# InputsExtras.net
KiCad netlist of a schematic drawn in Altium Designer
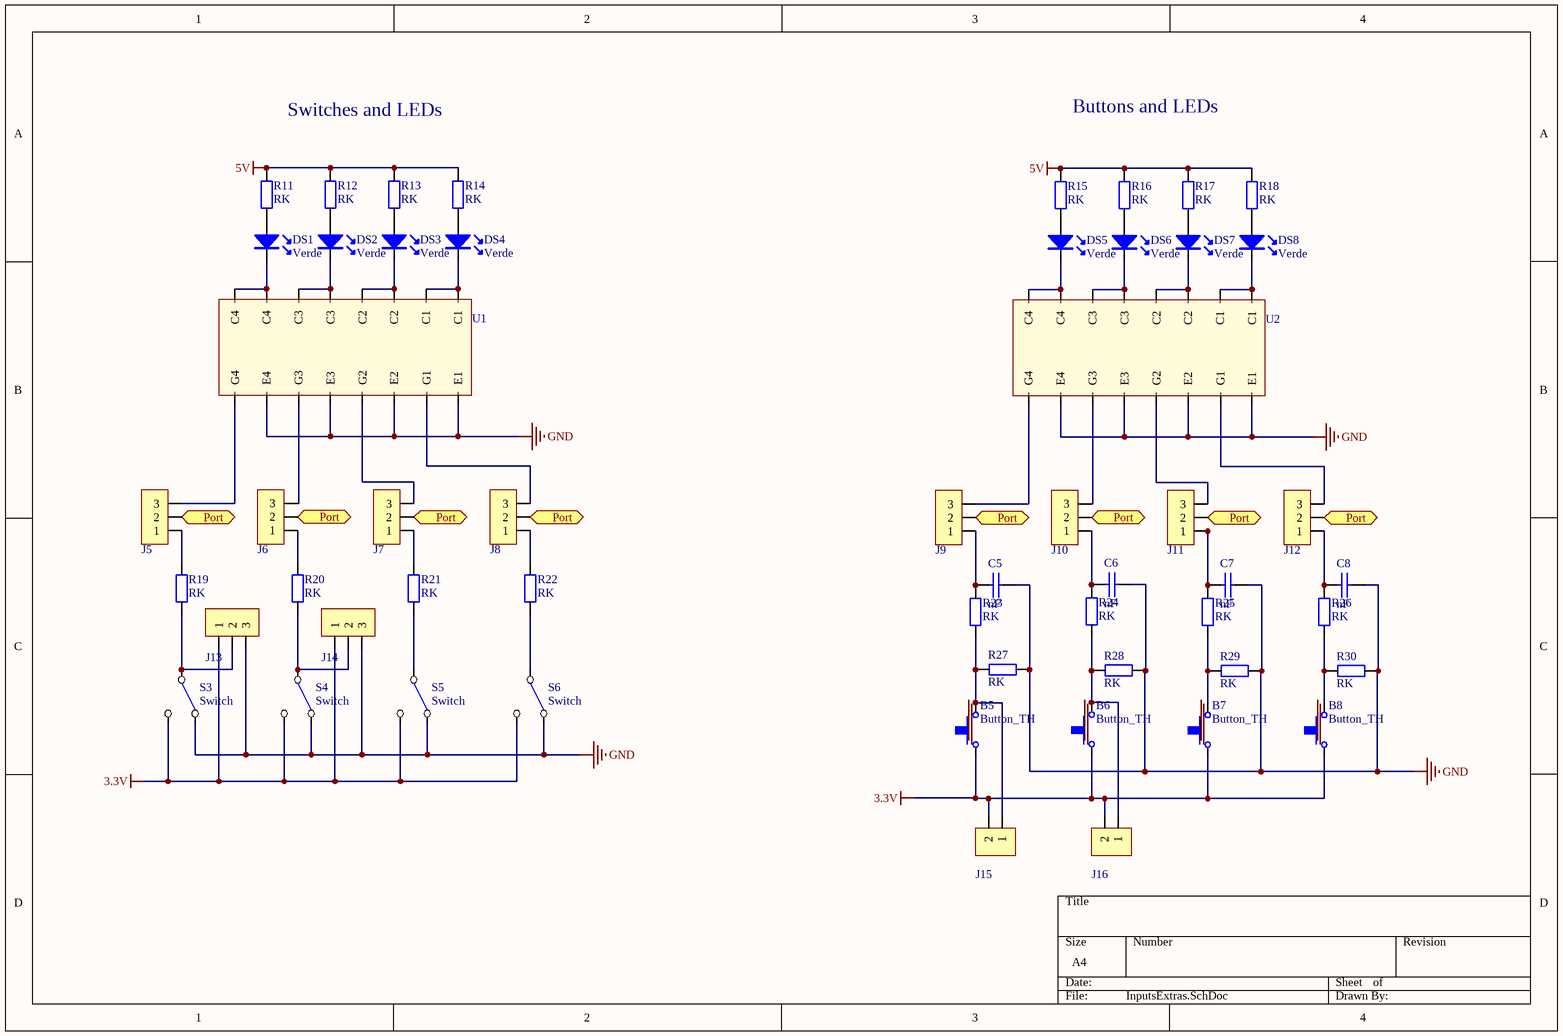
[diagram p0: InputsExtras.SchDoc]

(export (version "E")
  (design (tool "Eeschema 10.0.6"))
  (components
    (comp (ref "B5")
      (value "Button_TH")
      (footprint "ButtonTH")
      (libsource (lib "SCH_Lib") (part "Button_TH"))
    )
    (comp (ref "B6")
      (value "Button_TH")
      (footprint "ButtonTH")
      (libsource (lib "SCH_Lib") (part "Button_TH"))
    )
    (comp (ref "B7")
      (value "Button_TH")
      (footprint "ButtonTH")
      (libsource (lib "SCH_Lib") (part "Button_TH"))
    )
    (comp (ref "B8")
      (value "Button_TH")
      (footprint "ButtonTH")
      (libsource (lib "SCH_Lib") (part "Button_TH"))
    )
    (comp (ref "C5")
      (value "nF")
      (footprint "1206")
      (description "Condensador")
      (libsource (lib "SCH_Lib") (part "Condensador"))
    )
    (comp (ref "C6")
      (value "nF")
      (footprint "1206")
      (description "Condensador")
      (libsource (lib "SCH_Lib") (part "Condensador"))
    )
    (comp (ref "C7")
      (value "nF")
      (footprint "1206")
      (description "Condensador")
      (libsource (lib "SCH_Lib") (part "Condensador"))
    )
    (comp (ref "C8")
      (value "nF")
      (footprint "1206")
      (description "Condensador")
      (libsource (lib "SCH_Lib") (part "Condensador"))
    )
    (comp (ref "DS1") (value "Verde") (footprint "Led 3mm") (libsource (lib "SCH_Lib") (part "Led")))
    (comp (ref "DS2") (value "Verde") (footprint "Led 3mm") (libsource (lib "SCH_Lib") (part "Led")))
    (comp (ref "DS3") (value "Verde") (footprint "Led 3mm") (libsource (lib "SCH_Lib") (part "Led")))
    (comp (ref "DS4") (value "Verde") (footprint "Led 3mm") (libsource (lib "SCH_Lib") (part "Led")))
    (comp (ref "DS5") (value "Verde") (footprint "Led 3mm") (libsource (lib "SCH_Lib") (part "Led")))
    (comp (ref "DS6") (value "Verde") (footprint "Led 3mm") (libsource (lib "SCH_Lib") (part "Led")))
    (comp (ref "DS7") (value "Verde") (footprint "Led 3mm") (libsource (lib "SCH_Lib") (part "Led")))
    (comp (ref "DS8") (value "Verde") (footprint "Led 3mm") (libsource (lib "SCH_Lib") (part "Led")))
    (comp (ref "J5")
      (value "Cleva 2 vias")
      (footprint "con_3_100milis")
      (libsource (lib "SCH_Lib") (part "Con_3"))
    )
    (comp (ref "J6")
      (value "Cleva 2 vias")
      (footprint "con_3_100milis")
      (libsource (lib "SCH_Lib") (part "Con_3"))
    )
    (comp (ref "J7")
      (value "Cleva 2 vias")
      (footprint "con_3_100milis")
      (libsource (lib "SCH_Lib") (part "Con_3"))
    )
    (comp (ref "J8")
      (value "Cleva 2 vias")
      (footprint "con_3_100milis")
      (libsource (lib "SCH_Lib") (part "Con_3"))
    )
    (comp (ref "J9")
      (value "Cleva 2 vias")
      (footprint "con_3_100milis")
      (libsource (lib "SCH_Lib") (part "Con_3"))
    )
    (comp (ref "J10")
      (value "Cleva 2 vias")
      (footprint "con_3_100milis")
      (libsource (lib "SCH_Lib") (part "Con_3"))
    )
    (comp (ref "J11")
      (value "Cleva 2 vias")
      (footprint "con_3_100milis")
      (libsource (lib "SCH_Lib") (part "Con_3"))
    )
    (comp (ref "J12")
      (value "Cleva 2 vias")
      (footprint "con_3_100milis")
      (libsource (lib "SCH_Lib") (part "Con_3"))
    )
    (comp (ref "J13") (value "Cleva 2 vias") (footprint "Con3_KK_256") (libsource (lib "") (part "Con_3_1")))
    (comp (ref "J14") (value "Cleva 2 vias") (footprint "Con3_KK_256") (libsource (lib "") (part "Con_3_1")))
    (comp (ref "J15")
      (value "Cleva 2 vias")
      (footprint "Con2_KK_256")
      (libsource (lib "SCH_Lib") (part "Con_2"))
    )
    (comp (ref "J16")
      (value "Cleva 2 vias")
      (footprint "Con2_KK_256")
      (libsource (lib "SCH_Lib") (part "Con_2"))
    )
    (comp (ref "R11")
      (value "RK")
      (footprint "1206")
      (description "Resistencia")
      (libsource (lib "SCH_Lib") (part "Resistencia"))
    )
    (comp (ref "R12")
      (value "RK")
      (footprint "1206")
      (description "Resistencia")
      (libsource (lib "SCH_Lib") (part "Resistencia"))
    )
    (comp (ref "R13")
      (value "RK")
      (footprint "1206")
      (description "Resistencia")
      (libsource (lib "SCH_Lib") (part "Resistencia"))
    )
    (comp (ref "R14")
      (value "RK")
      (footprint "1206")
      (description "Resistencia")
      (libsource (lib "SCH_Lib") (part "Resistencia"))
    )
    (comp (ref "R15")
      (value "RK")
      (footprint "1206")
      (description "Resistencia")
      (libsource (lib "SCH_Lib") (part "Resistencia"))
    )
    (comp (ref "R16")
      (value "RK")
      (footprint "1206")
      (description "Resistencia")
      (libsource (lib "SCH_Lib") (part "Resistencia"))
    )
    (comp (ref "R17")
      (value "RK")
      (footprint "1206")
      (description "Resistencia")
      (libsource (lib "SCH_Lib") (part "Resistencia"))
    )
    (comp (ref "R18")
      (value "RK")
      (footprint "1206")
      (description "Resistencia")
      (libsource (lib "SCH_Lib") (part "Resistencia"))
    )
    (comp (ref "R19")
      (value "RK")
      (footprint "1206")
      (description "Resistencia")
      (libsource (lib "SCH_Lib") (part "Resistencia"))
    )
    (comp (ref "R20")
      (value "RK")
      (footprint "1206")
      (description "Resistencia")
      (libsource (lib "SCH_Lib") (part "Resistencia"))
    )
    (comp (ref "R21")
      (value "RK")
      (footprint "1206")
      (description "Resistencia")
      (libsource (lib "SCH_Lib") (part "Resistencia"))
    )
    (comp (ref "R22")
      (value "RK")
      (footprint "1206")
      (description "Resistencia")
      (libsource (lib "SCH_Lib") (part "Resistencia"))
    )
    (comp (ref "R23")
      (value "RK")
      (footprint "1206")
      (description "Resistencia")
      (libsource (lib "SCH_Lib") (part "Resistencia"))
    )
    (comp (ref "R24")
      (value "RK")
      (footprint "1206")
      (description "Resistencia")
      (libsource (lib "SCH_Lib") (part "Resistencia"))
    )
    (comp (ref "R25")
      (value "RK")
      (footprint "1206")
      (description "Resistencia")
      (libsource (lib "SCH_Lib") (part "Resistencia"))
    )
    (comp (ref "R26")
      (value "RK")
      (footprint "1206")
      (description "Resistencia")
      (libsource (lib "SCH_Lib") (part "Resistencia"))
    )
    (comp (ref "R27")
      (value "RK")
      (footprint "1206")
      (description "Resistencia")
      (libsource (lib "SCH_Lib") (part "Resistencia"))
    )
    (comp (ref "R28")
      (value "RK")
      (footprint "1206")
      (description "Resistencia")
      (libsource (lib "SCH_Lib") (part "Resistencia"))
    )
    (comp (ref "R29")
      (value "RK")
      (footprint "1206")
      (description "Resistencia")
      (libsource (lib "SCH_Lib") (part "Resistencia"))
    )
    (comp (ref "R30")
      (value "RK")
      (footprint "1206")
      (description "Resistencia")
      (libsource (lib "SCH_Lib") (part "Resistencia"))
    )
    (comp (ref "S3") (value "Switch") (footprint "SwitchTH_2Pos") (libsource (lib "SCH_Lib") (part "Switch")))
    (comp (ref "S4") (value "Switch") (footprint "SwitchTH_2Pos") (libsource (lib "SCH_Lib") (part "Switch")))
    (comp (ref "S5") (value "Switch") (footprint "SwitchTH_2Pos") (libsource (lib "SCH_Lib") (part "Switch")))
    (comp (ref "S6") (value "Switch") (footprint "SwitchTH_2Pos") (libsource (lib "SCH_Lib") (part "Switch")))
    (comp (ref "U1") (value "MMPQ3904") (footprint "SO-16") (libsource (lib "SCH_Lib") (part "MMPQ3904")))
    (comp (ref "U2") (value "MMPQ3904") (footprint "SO-16") (libsource (lib "SCH_Lib") (part "MMPQ3904")))
  )
  (nets
    (net (code "1") (name "/Port") (class "Default")
      (node (ref "J10") (pin "2") (pinfunction "2_2") (pintype "passive"))
      (node (ref "J11") (pin "2") (pinfunction "2_2") (pintype "passive"))
      (node (ref "J12") (pin "2") (pinfunction "2_2") (pintype "passive"))
      (node (ref "J5") (pin "2") (pinfunction "2_2") (pintype "passive"))
      (node (ref "J6") (pin "2") (pinfunction "2_2") (pintype "passive"))
      (node (ref "J7") (pin "2") (pinfunction "2_2") (pintype "passive"))
      (node (ref "J8") (pin "2") (pinfunction "2_2") (pintype "passive"))
      (node (ref "J9") (pin "2") (pinfunction "2_2") (pintype "passive"))
    )
    (net (code "2") (name "3.3V") (class "Default")
      (node (ref "B5") (pin "1") (pinfunction "1_1") (pintype "passive"))
      (node (ref "B6") (pin "1") (pinfunction "1_1") (pintype "passive"))
      (node (ref "B7") (pin "1") (pinfunction "1_1") (pintype "passive"))
      (node (ref "B8") (pin "1") (pinfunction "1_1") (pintype "passive"))
      (node (ref "J13") (pin "1") (pinfunction "1_1") (pintype "passive"))
      (node (ref "J14") (pin "1") (pinfunction "1_1") (pintype "passive"))
      (node (ref "J15") (pin "2") (pinfunction "2_2") (pintype "passive"))
      (node (ref "J16") (pin "2") (pinfunction "2_2") (pintype "passive"))
      (node (ref "S3") (pin "2") (pinfunction "ON2_2") (pintype "passive"))
      (node (ref "S4") (pin "2") (pinfunction "ON2_2") (pintype "passive"))
      (node (ref "S5") (pin "2") (pinfunction "ON2_2") (pintype "passive"))
      (node (ref "S6") (pin "2") (pinfunction "ON2_2") (pintype "passive"))
    )
    (net (code "3") (name "5V") (class "Default")
      (node (ref "R11") (pin "1") (pinfunction "1_1") (pintype "passive"))
      (node (ref "R12") (pin "1") (pinfunction "1_1") (pintype "passive"))
      (node (ref "R13") (pin "1") (pinfunction "1_1") (pintype "passive"))
      (node (ref "R14") (pin "1") (pinfunction "1_1") (pintype "passive"))
      (node (ref "R15") (pin "1") (pinfunction "1_1") (pintype "passive"))
      (node (ref "R16") (pin "1") (pinfunction "1_1") (pintype "passive"))
      (node (ref "R17") (pin "1") (pinfunction "1_1") (pintype "passive"))
      (node (ref "R18") (pin "1") (pinfunction "1_1") (pintype "passive"))
    )
    (net (code "4") (name "GND") (class "Default")
      (node (ref "C5") (pin "1") (pintype "passive"))
      (node (ref "C6") (pin "1") (pintype "passive"))
      (node (ref "C7") (pin "1") (pintype "passive"))
      (node (ref "C8") (pin "1") (pintype "passive"))
      (node (ref "J13") (pin "3") (pinfunction "3_3") (pintype "passive"))
      (node (ref "J14") (pin "3") (pinfunction "3_3") (pintype "passive"))
      (node (ref "R27") (pin "1") (pinfunction "1_1") (pintype "passive"))
      (node (ref "R28") (pin "1") (pinfunction "1_1") (pintype "passive"))
      (node (ref "R29") (pin "1") (pinfunction "1_1") (pintype "passive"))
      (node (ref "R30") (pin "1") (pinfunction "1_1") (pintype "passive"))
      (node (ref "S3") (pin "0") (pinfunction "ON1_0") (pintype "passive"))
      (node (ref "S4") (pin "0") (pinfunction "ON1_0") (pintype "passive"))
      (node (ref "S5") (pin "0") (pinfunction "ON1_0") (pintype "passive"))
      (node (ref "S6") (pin "0") (pinfunction "ON1_0") (pintype "passive"))
      (node (ref "U1") (pin "10") (pinfunction "E4_10") (pintype "passive"))
      (node (ref "U1") (pin "12") (pinfunction "E3_12") (pintype "passive"))
      (node (ref "U1") (pin "14") (pinfunction "E2_14") (pintype "passive"))
      (node (ref "U1") (pin "16") (pinfunction "E1_16") (pintype "passive"))
      (node (ref "U2") (pin "10") (pinfunction "E4_10") (pintype "passive"))
      (node (ref "U2") (pin "12") (pinfunction "E3_12") (pintype "passive"))
      (node (ref "U2") (pin "14") (pinfunction "E2_14") (pintype "passive"))
      (node (ref "U2") (pin "16") (pinfunction "E1_16") (pintype "passive"))
    )
    (net (code "5") (name "Net-(B5-Pad0)") (class "Default")
      (node (ref "B5") (pin "0") (pinfunction "0_0") (pintype "passive"))
      (node (ref "J15") (pin "1") (pinfunction "1_1") (pintype "passive"))
      (node (ref "R23") (pin "1") (pinfunction "1_1") (pintype "passive"))
      (node (ref "R27") (pin "2") (pinfunction "2_2") (pintype "passive"))
    )
    (net (code "6") (name "Net-(B6-Pad0)") (class "Default")
      (node (ref "B6") (pin "0") (pinfunction "0_0") (pintype "passive"))
      (node (ref "J16") (pin "1") (pinfunction "1_1") (pintype "passive"))
      (node (ref "R24") (pin "1") (pinfunction "1_1") (pintype "passive"))
      (node (ref "R28") (pin "2") (pinfunction "2_2") (pintype "passive"))
    )
    (net (code "7") (name "Net-(B7-Pad0)") (class "Default")
      (node (ref "B7") (pin "0") (pinfunction "0_0") (pintype "passive"))
      (node (ref "R25") (pin "1") (pinfunction "1_1") (pintype "passive"))
      (node (ref "R29") (pin "2") (pinfunction "2_2") (pintype "passive"))
    )
    (net (code "8") (name "Net-(B8-Pad0)") (class "Default")
      (node (ref "B8") (pin "0") (pinfunction "0_0") (pintype "passive"))
      (node (ref "R26") (pin "1") (pinfunction "1_1") (pintype "passive"))
      (node (ref "R30") (pin "2") (pinfunction "2_2") (pintype "passive"))
    )
    (net (code "9") (name "Net-(C5-Pad2)") (class "Default")
      (node (ref "C5") (pin "2") (pintype "passive"))
      (node (ref "J9") (pin "1") (pinfunction "1_1") (pintype "passive"))
      (node (ref "R23") (pin "2") (pinfunction "2_2") (pintype "passive"))
    )
    (net (code "10") (name "Net-(C6-Pad2)") (class "Default")
      (node (ref "C6") (pin "2") (pintype "passive"))
      (node (ref "J10") (pin "1") (pinfunction "1_1") (pintype "passive"))
      (node (ref "R24") (pin "2") (pinfunction "2_2") (pintype "passive"))
    )
    (net (code "11") (name "Net-(C7-Pad2)") (class "Default")
      (node (ref "C7") (pin "2") (pintype "passive"))
      (node (ref "J11") (pin "1") (pinfunction "1_1") (pintype "passive"))
      (node (ref "R25") (pin "2") (pinfunction "2_2") (pintype "passive"))
    )
    (net (code "12") (name "Net-(C8-Pad2)") (class "Default")
      (node (ref "C8") (pin "2") (pintype "passive"))
      (node (ref "J12") (pin "1") (pinfunction "1_1") (pintype "passive"))
      (node (ref "R26") (pin "2") (pinfunction "2_2") (pintype "passive"))
    )
    (net (code "13") (name "Net-(DS1-PadA)") (class "Default")
      (node (ref "DS1") (pin "A") (pinfunction "A_A") (pintype "passive"))
      (node (ref "R11") (pin "2") (pinfunction "2_2") (pintype "passive"))
    )
    (net (code "14") (name "Net-(DS1-PadK)") (class "Default")
      (node (ref "DS1") (pin "K") (pinfunction "K_K") (pintype "passive"))
      (node (ref "U1") (pin "7") (pinfunction "C4_7") (pintype "passive"))
      (node (ref "U1") (pin "8") (pinfunction "C4_8") (pintype "passive"))
    )
    (net (code "15") (name "Net-(DS2-PadA)") (class "Default")
      (node (ref "DS2") (pin "A") (pinfunction "A_A") (pintype "passive"))
      (node (ref "R12") (pin "2") (pinfunction "2_2") (pintype "passive"))
    )
    (net (code "16") (name "Net-(DS2-PadK)") (class "Default")
      (node (ref "DS2") (pin "K") (pinfunction "K_K") (pintype "passive"))
      (node (ref "U1") (pin "5") (pinfunction "C3_5") (pintype "passive"))
      (node (ref "U1") (pin "6") (pinfunction "C3_6") (pintype "passive"))
    )
    (net (code "17") (name "Net-(DS3-PadA)") (class "Default")
      (node (ref "DS3") (pin "A") (pinfunction "A_A") (pintype "passive"))
      (node (ref "R13") (pin "2") (pinfunction "2_2") (pintype "passive"))
    )
    (net (code "18") (name "Net-(DS3-PadK)") (class "Default")
      (node (ref "DS3") (pin "K") (pinfunction "K_K") (pintype "passive"))
      (node (ref "U1") (pin "3") (pinfunction "C2_3") (pintype "passive"))
      (node (ref "U1") (pin "4") (pinfunction "C2_4") (pintype "passive"))
    )
    (net (code "19") (name "Net-(DS4-PadA)") (class "Default")
      (node (ref "DS4") (pin "A") (pinfunction "A_A") (pintype "passive"))
      (node (ref "R14") (pin "2") (pinfunction "2_2") (pintype "passive"))
    )
    (net (code "20") (name "Net-(DS4-PadK)") (class "Default")
      (node (ref "DS4") (pin "K") (pinfunction "K_K") (pintype "passive"))
      (node (ref "U1") (pin "1") (pinfunction "C1_1") (pintype "passive"))
      (node (ref "U1") (pin "2") (pinfunction "C1_2") (pintype "passive"))
    )
    (net (code "21") (name "Net-(DS5-PadA)") (class "Default")
      (node (ref "DS5") (pin "A") (pinfunction "A_A") (pintype "passive"))
      (node (ref "R15") (pin "2") (pinfunction "2_2") (pintype "passive"))
    )
    (net (code "22") (name "Net-(DS5-PadK)") (class "Default")
      (node (ref "DS5") (pin "K") (pinfunction "K_K") (pintype "passive"))
      (node (ref "U2") (pin "7") (pinfunction "C4_7") (pintype "passive"))
      (node (ref "U2") (pin "8") (pinfunction "C4_8") (pintype "passive"))
    )
    (net (code "23") (name "Net-(DS6-PadA)") (class "Default")
      (node (ref "DS6") (pin "A") (pinfunction "A_A") (pintype "passive"))
      (node (ref "R16") (pin "2") (pinfunction "2_2") (pintype "passive"))
    )
    (net (code "24") (name "Net-(DS6-PadK)") (class "Default")
      (node (ref "DS6") (pin "K") (pinfunction "K_K") (pintype "passive"))
      (node (ref "U2") (pin "5") (pinfunction "C3_5") (pintype "passive"))
      (node (ref "U2") (pin "6") (pinfunction "C3_6") (pintype "passive"))
    )
    (net (code "25") (name "Net-(DS7-PadA)") (class "Default")
      (node (ref "DS7") (pin "A") (pinfunction "A_A") (pintype "passive"))
      (node (ref "R17") (pin "2") (pinfunction "2_2") (pintype "passive"))
    )
    (net (code "26") (name "Net-(DS7-PadK)") (class "Default")
      (node (ref "DS7") (pin "K") (pinfunction "K_K") (pintype "passive"))
      (node (ref "U2") (pin "3") (pinfunction "C2_3") (pintype "passive"))
      (node (ref "U2") (pin "4") (pinfunction "C2_4") (pintype "passive"))
    )
    (net (code "27") (name "Net-(DS8-PadA)") (class "Default")
      (node (ref "DS8") (pin "A") (pinfunction "A_A") (pintype "passive"))
      (node (ref "R18") (pin "2") (pinfunction "2_2") (pintype "passive"))
    )
    (net (code "28") (name "Net-(DS8-PadK)") (class "Default")
      (node (ref "DS8") (pin "K") (pinfunction "K_K") (pintype "passive"))
      (node (ref "U2") (pin "1") (pinfunction "C1_1") (pintype "passive"))
      (node (ref "U2") (pin "2") (pinfunction "C1_2") (pintype "passive"))
    )
    (net (code "29") (name "Net-(J5-Pad1)") (class "Default")
      (node (ref "J5") (pin "1") (pinfunction "1_1") (pintype "passive"))
      (node (ref "R19") (pin "2") (pinfunction "2_2") (pintype "passive"))
    )
    (net (code "30") (name "Net-(J6-Pad1)") (class "Default")
      (node (ref "J6") (pin "1") (pinfunction "1_1") (pintype "passive"))
      (node (ref "R20") (pin "2") (pinfunction "2_2") (pintype "passive"))
    )
    (net (code "31") (name "Net-(J7-Pad1)") (class "Default")
      (node (ref "J7") (pin "1") (pinfunction "1_1") (pintype "passive"))
      (node (ref "R21") (pin "2") (pinfunction "2_2") (pintype "passive"))
    )
    (net (code "32") (name "Net-(J8-Pad1)") (class "Default")
      (node (ref "J8") (pin "1") (pinfunction "1_1") (pintype "passive"))
      (node (ref "R22") (pin "2") (pinfunction "2_2") (pintype "passive"))
    )
    (net (code "33") (name "Net-(S3-COMMON)") (class "Default")
      (node (ref "J13") (pin "2") (pinfunction "2_2") (pintype "passive"))
      (node (ref "R19") (pin "1") (pinfunction "1_1") (pintype "passive"))
      (node (ref "S3") (pin "1") (pinfunction "COMMON_1") (pintype "passive"))
    )
    (net (code "34") (name "Net-(S4-COMMON)") (class "Default")
      (node (ref "J14") (pin "2") (pinfunction "2_2") (pintype "passive"))
      (node (ref "R20") (pin "1") (pinfunction "1_1") (pintype "passive"))
      (node (ref "S4") (pin "1") (pinfunction "COMMON_1") (pintype "passive"))
    )
    (net (code "35") (name "Net-(S5-COMMON)") (class "Default")
      (node (ref "R21") (pin "1") (pinfunction "1_1") (pintype "passive"))
      (node (ref "S5") (pin "1") (pinfunction "COMMON_1") (pintype "passive"))
    )
    (net (code "36") (name "Net-(S6-COMMON)") (class "Default")
      (node (ref "R22") (pin "1") (pinfunction "1_1") (pintype "passive"))
      (node (ref "S6") (pin "1") (pinfunction "COMMON_1") (pintype "passive"))
    )
    (net (code "37") (name "Net-(U1-G1)") (class "Default")
      (node (ref "J8") (pin "3") (pinfunction "3_3") (pintype "passive"))
      (node (ref "U1") (pin "15") (pinfunction "G1_15") (pintype "passive"))
    )
    (net (code "38") (name "Net-(U1-G2)") (class "Default")
      (node (ref "J7") (pin "3") (pinfunction "3_3") (pintype "passive"))
      (node (ref "U1") (pin "13") (pinfunction "G2_13") (pintype "passive"))
    )
    (net (code "39") (name "Net-(U1-G3)") (class "Default")
      (node (ref "J6") (pin "3") (pinfunction "3_3") (pintype "passive"))
      (node (ref "U1") (pin "11") (pinfunction "G3_11") (pintype "passive"))
    )
    (net (code "40") (name "Net-(U1-G4)") (class "Default")
      (node (ref "J5") (pin "3") (pinfunction "3_3") (pintype "passive"))
      (node (ref "U1") (pin "9") (pinfunction "G4_9") (pintype "passive"))
    )
    (net (code "41") (name "Net-(U2-G1)") (class "Default")
      (node (ref "J12") (pin "3") (pinfunction "3_3") (pintype "passive"))
      (node (ref "U2") (pin "15") (pinfunction "G1_15") (pintype "passive"))
    )
    (net (code "42") (name "Net-(U2-G2)") (class "Default")
      (node (ref "J11") (pin "3") (pinfunction "3_3") (pintype "passive"))
      (node (ref "U2") (pin "13") (pinfunction "G2_13") (pintype "passive"))
    )
    (net (code "43") (name "Net-(U2-G3)") (class "Default")
      (node (ref "J10") (pin "3") (pinfunction "3_3") (pintype "passive"))
      (node (ref "U2") (pin "11") (pinfunction "G3_11") (pintype "passive"))
    )
    (net (code "44") (name "Net-(U2-G4)") (class "Default")
      (node (ref "J9") (pin "3") (pinfunction "3_3") (pintype "passive"))
      (node (ref "U2") (pin "9") (pinfunction "G4_9") (pintype "passive"))
    )
  )
)
